# Modulo_vers_o_10.net
KiCad netlist of a schematic drawn in EAGLE
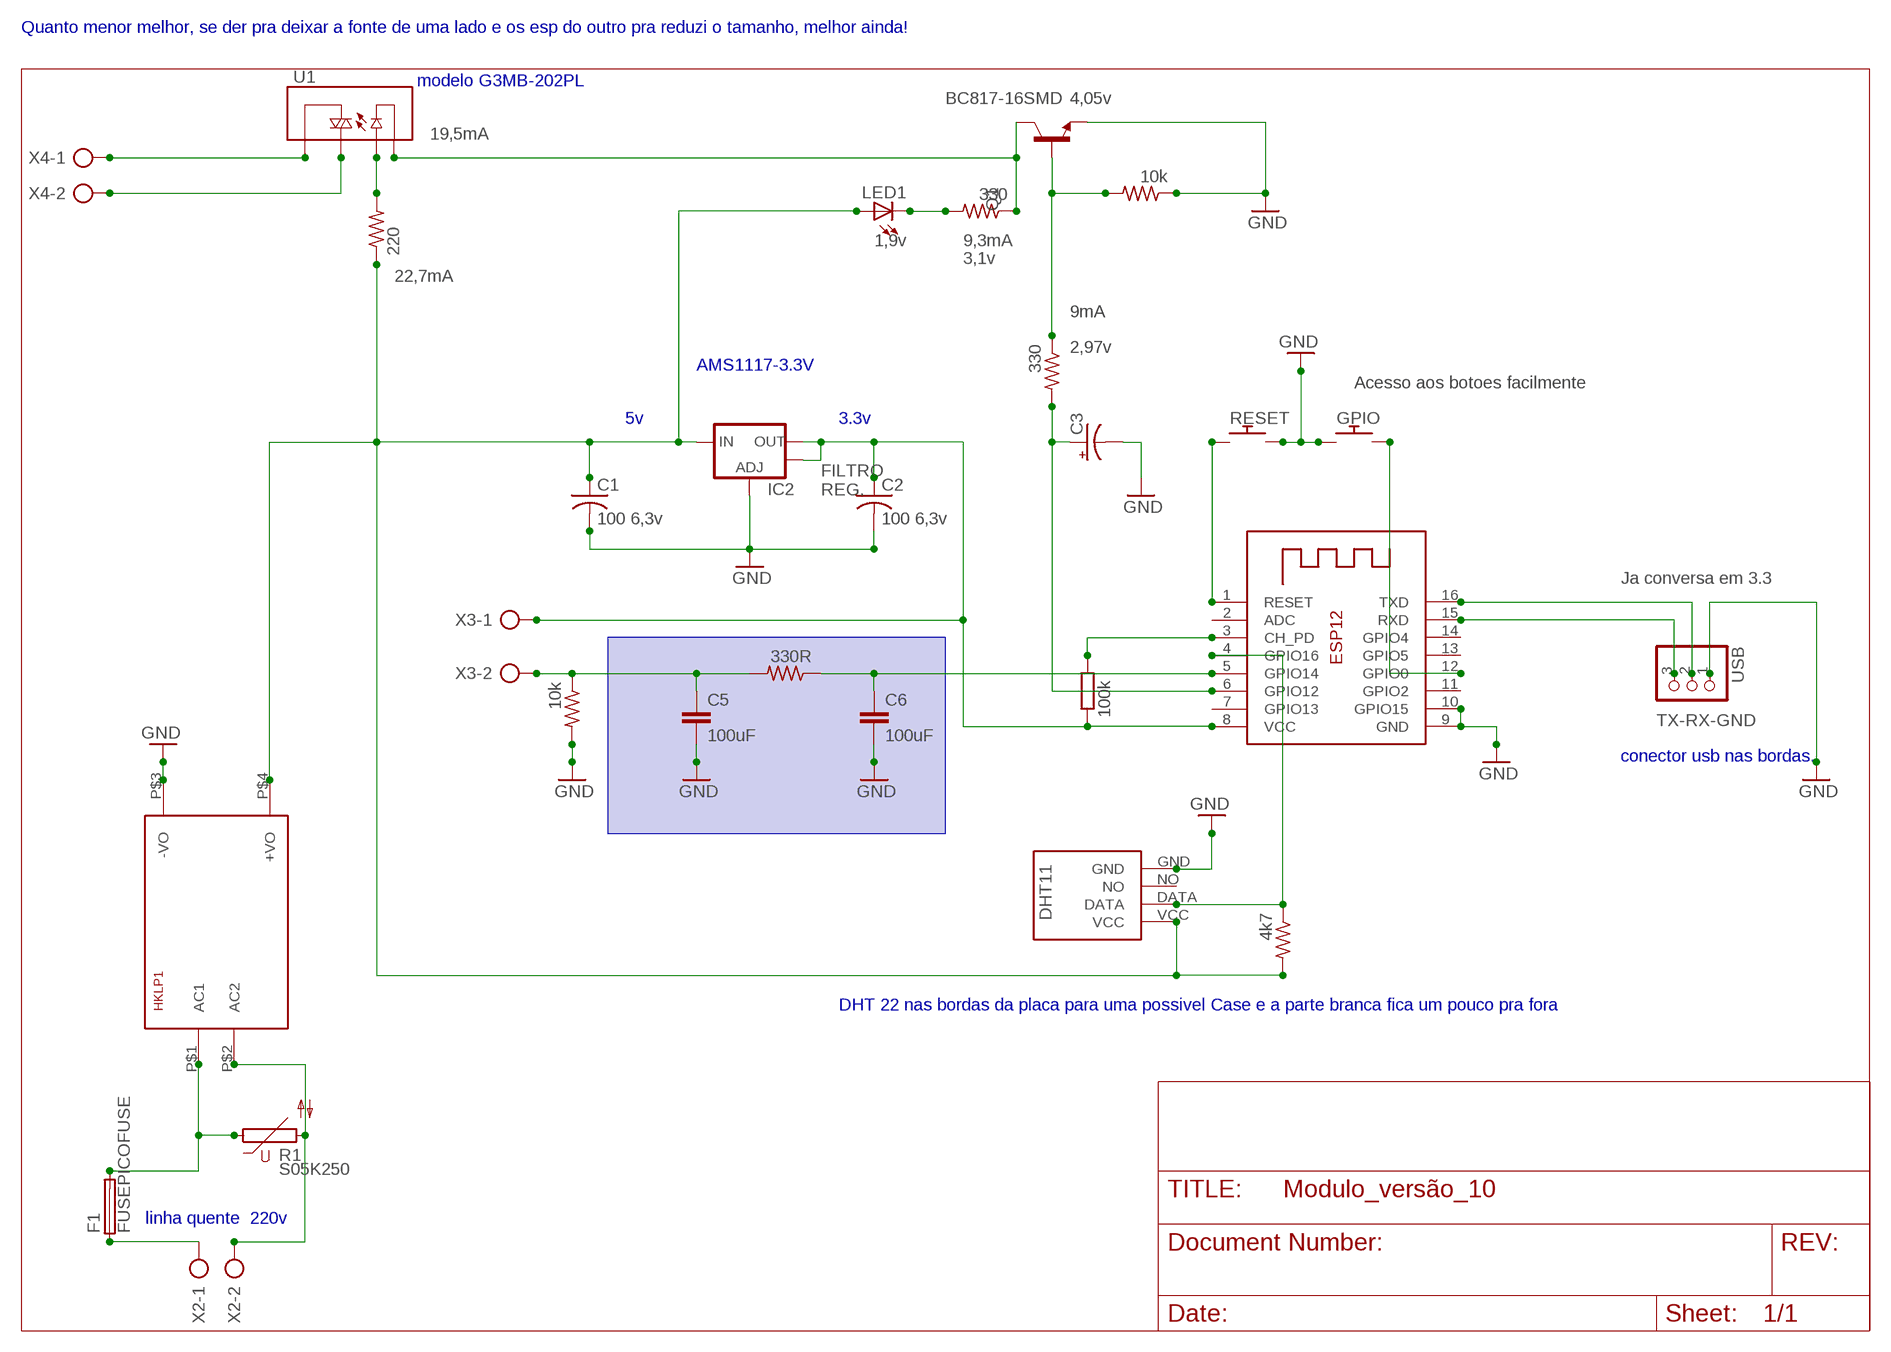
[diagram p0: schematic, sheet 1]

(export (version "E")
  (design (tool "Eeschema 10.0.6"))
  (components
    (comp (ref "1")
      (value "10k")
      (footprint "eagle-import:M0805")
      (libsource (lib "eagle-import") (part "R-US_M0805"))
    )
    (comp (ref "2")
      (value "10k")
      (footprint "eagle-import:M0805")
      (libsource (lib "eagle-import") (part "R-US_M0805"))
    )
    (comp (ref "3")
      (value "100k")
      (footprint "eagle-import:M0805")
      (libsource (lib "eagle-import") (part "R-EU_M0805"))
    )
    (comp (ref "4")
      (value "330R")
      (footprint "eagle-import:M0805")
      (libsource (lib "eagle-import") (part "R-US_M0805"))
    )
    (comp (ref "5")
      (value "330")
      (footprint "eagle-import:M0805")
      (libsource (lib "eagle-import") (part "R-US_M0805"))
    )
    (comp (ref "6")
      (value "220")
      (footprint "eagle-import:M0805")
      (libsource (lib "eagle-import") (part "R-US_M0805"))
    )
    (comp (ref "7")
      (value "330")
      (footprint "eagle-import:M0805")
      (libsource (lib "eagle-import") (part "R-US_M0805"))
    )
    (comp (ref "8")
      (value "4k7")
      (footprint "eagle-import:M0805")
      (libsource (lib "eagle-import") (part "R-US_M0805"))
    )
    (comp (ref "C1")
      (value "100 6,3v")
      (footprint "eagle-import:C0805")
      (libsource (lib "eagle-import") (part "C-USC0805"))
    )
    (comp (ref "C2")
      (value "100 6,3v")
      (footprint "eagle-import:C0805")
      (libsource (lib "eagle-import") (part "C-USC0805"))
    )
    (comp (ref "C3")
      (value "CPOL-US153CLV-0605")
      (footprint "eagle-import:153CLV-0605")
      (libsource (lib "eagle-import") (part "CPOL-US153CLV-0605"))
    )
    (comp (ref "C5")
      (value "100uF")
      (footprint "eagle-import:C0805")
      (libsource (lib "eagle-import") (part "C-EUC0805"))
    )
    (comp (ref "C6")
      (value "100uF")
      (footprint "eagle-import:C0805")
      (libsource (lib "eagle-import") (part "C-EUC0805"))
    )
    (comp (ref "F1")
      (value "FUSEPICOFUSE")
      (footprint "eagle-import:PICOFUSE")
      (libsource (lib "eagle-import") (part "FUSEPICOFUSE"))
    )
    (comp (ref "GPIO")
      (value "GPIO")
      (footprint "eagle-import:TACT_PANA-EVQ")
      (libsource (lib "eagle-import") (part "SWITCH_PUSHBUTTONEVQ-PE"))
    )
    (comp (ref "HKLP1")
      (value "HKLPM01")
      (footprint "eagle-import:HKLPM01")
      (libsource (lib "eagle-import") (part "HKLPM01"))
    )
    (comp (ref "IC2")
      (value "V_REG_LM1117SOT223")
      (footprint "eagle-import:SOT223")
      (libsource (lib "eagle-import") (part "V_REG_LM1117SOT223"))
    )
    (comp (ref "LED1")
      (value "LEDCHIPLED_0805")
      (footprint "eagle-import:CHIPLED_0805")
      (libsource (lib "eagle-import") (part "LEDCHIPLED_0805"))
    )
    (comp (ref "Q1")
      (value "BC817-16SMD")
      (footprint "eagle-import:SOT23-BEC")
      (libsource (lib "eagle-import") (part "BC817SMD-16"))
    )
    (comp (ref "R1")
      (value "S05K250")
      (footprint "eagle-import:S05K250")
      (libsource (lib "eagle-import") (part "S05K250"))
    )
    (comp (ref "RESET")
      (value "RESET")
      (footprint "eagle-import:TACT_PANA-EVQ")
      (libsource (lib "eagle-import") (part "SWITCH_PUSHBUTTONEVQ-PE"))
    )
    (comp (ref "U$1")
      (value "DHT11-PION.")
      (footprint "eagle-import:DHT11-PION.")
      (libsource (lib "eagle-import") (part "DHT11-PION."))
    )
    (comp (ref "U1")
      (value "RELAY-SOLIDSTATEPTH")
      (footprint "eagle-import:RELAY-S108T02")
      (libsource (lib "eagle-import") (part "RELAY-SOLIDSTATEPTH"))
    )
    (comp (ref "USB")
      (value "PINHD-1X3")
      (footprint "eagle-import:1X03")
      (libsource (lib "eagle-import") (part "PINHD-1X3"))
    )
    (comp (ref "X2")
      (value "AK500/2")
      (footprint "eagle-import:AK500_2")
      (libsource (lib "eagle-import") (part "AK500/2"))
    )
    (comp (ref "X3")
      (value "AK500/2")
      (footprint "eagle-import:AK500_2")
      (libsource (lib "eagle-import") (part "AK500/2"))
    )
    (comp (ref "X4")
      (value "AK500/2")
      (footprint "eagle-import:AK500_2")
      (libsource (lib "eagle-import") (part "AK500/2"))
    )
    (comp (ref "X5")
      (value "ESP-12")
      (footprint "eagle-import:ESP-12")
      (libsource (lib "eagle-import") (part "ESP-12"))
    )
  )
  (nets
    (net (code "1") (name "GND") (class "Default")
      (node (ref "1") (pin "1") (pinfunction "1_1") (pintype "passive"))
      (node (ref "2") (pin "2") (pinfunction "2_2") (pintype "passive"))
      (node (ref "C1") (pin "2") (pinfunction "2_2") (pintype "passive"))
      (node (ref "C2") (pin "2") (pinfunction "2_2") (pintype "passive"))
      (node (ref "C3") (pin "-") (pinfunction "-_-") (pintype "passive"))
      (node (ref "C5") (pin "2") (pinfunction "2_2") (pintype "passive"))
      (node (ref "C6") (pin "2") (pinfunction "2_2") (pintype "passive"))
      (node (ref "GPIO") (pin "P$1") (pinfunction "P$1_P$1") (pintype "passive"))
      (node (ref "HKLP1") (pin "P$3") (pinfunction "-VO_P$3") (pintype "bidirectional"))
      (node (ref "IC2") (pin "1") (pinfunction "ADJ_1") (pintype "input"))
      (node (ref "Q1") (pin "E") (pinfunction "E_E") (pintype "passive"))
      (node (ref "RESET") (pin "P$2") (pinfunction "P$2_P$2") (pintype "passive"))
      (node (ref "U$1") (pin "GND") (pinfunction "GND_GND") (pintype "bidirectional"))
      (node (ref "USB") (pin "1") (pinfunction "1_1") (pintype "passive"))
      (node (ref "X5") (pin "10") (pinfunction "GPIO15_10") (pintype "bidirectional"))
      (node (ref "X5") (pin "9") (pinfunction "GND_9") (pintype "power_in"))
    )
    (net (code "2") (name "Net-(1-Pad2)") (class "Default")
      (node (ref "1") (pin "2") (pinfunction "2_2") (pintype "passive"))
      (node (ref "7") (pin "1") (pinfunction "1_1") (pintype "passive"))
      (node (ref "Q1") (pin "B") (pinfunction "B_B") (pintype "passive"))
    )
    (net (code "3") (name "Net-(5-Pad2)") (class "Default")
      (node (ref "5") (pin "2") (pinfunction "2_2") (pintype "passive"))
      (node (ref "LED1") (pin "C") (pinfunction "C_C") (pintype "passive"))
    )
    (net (code "4") (name "Net-(HKLP1-+VO)") (class "Default")
      (node (ref "6") (pin "1") (pinfunction "1_1") (pintype "passive"))
      (node (ref "8") (pin "2") (pinfunction "2_2") (pintype "passive"))
      (node (ref "C1") (pin "1") (pinfunction "1_1") (pintype "passive"))
      (node (ref "HKLP1") (pin "P$4") (pinfunction "+VO_P$4") (pintype "bidirectional"))
      (node (ref "IC2") (pin "3") (pinfunction "IN_3") (pintype "input"))
      (node (ref "LED1") (pin "A") (pinfunction "A_A") (pintype "passive"))
      (node (ref "U$1") (pin "VCC") (pinfunction "VCC_VCC") (pintype "bidirectional"))
    )
    (net (code "5") (name "Net-(HKLP1-AC1)") (class "Default")
      (node (ref "F1") (pin "2") (pinfunction "2_2") (pintype "passive"))
      (node (ref "HKLP1") (pin "P$1") (pinfunction "AC1_P$1") (pintype "bidirectional"))
      (node (ref "R1") (pin "1") (pinfunction "1_1") (pintype "passive"))
    )
    (net (code "6") (name "Net-(HKLP1-AC2)") (class "Default")
      (node (ref "HKLP1") (pin "P$2") (pinfunction "AC2_P$2") (pintype "bidirectional"))
      (node (ref "R1") (pin "2") (pinfunction "2_2") (pintype "passive"))
      (node (ref "X2") (pin "2") (pinfunction "KL_2") (pintype "passive"))
    )
    (net (code "7") (name "Net-(U1-+)") (class "Default")
      (node (ref "6") (pin "2") (pinfunction "2_2") (pintype "passive"))
      (node (ref "U1") (pin "3") (pinfunction "+_3") (pintype "bidirectional"))
    )
    (net (code "8") (name "Net-(U1--)") (class "Default")
      (node (ref "5") (pin "1") (pinfunction "1_1") (pintype "passive"))
      (node (ref "Q1") (pin "C") (pinfunction "C_C") (pintype "passive"))
      (node (ref "U1") (pin "4") (pinfunction "-_4") (pintype "bidirectional"))
    )
    (net (code "9") (name "Net-(U1-T1)") (class "Default")
      (node (ref "U1") (pin "1") (pinfunction "T1_1") (pintype "bidirectional"))
      (node (ref "X4") (pin "1") (pinfunction "KL_1") (pintype "passive"))
    )
    (net (code "10") (name "Net-(U1-T2)") (class "Default")
      (node (ref "U1") (pin "2") (pinfunction "T2_2") (pintype "bidirectional"))
      (node (ref "X4") (pin "2") (pinfunction "KL_2") (pintype "passive"))
    )
    (net (code "11") (name "Net-(X2A-KL)") (class "Default")
      (node (ref "F1") (pin "1") (pinfunction "1_1") (pintype "passive"))
      (node (ref "X2") (pin "1") (pinfunction "KL_1") (pintype "passive"))
    )
    (net (code "12") (name "Net-(X3A-KL)") (class "Default")
      (node (ref "3") (pin "1") (pinfunction "1_1") (pintype "passive"))
      (node (ref "C2") (pin "1") (pinfunction "1_1") (pintype "passive"))
      (node (ref "IC2") (pin "2") (pinfunction "OUT_2") (pintype "output"))
      (node (ref "IC2") (pin "4") (pinfunction "OUT_4") (pintype "output"))
      (node (ref "X3") (pin "1") (pinfunction "KL_1") (pintype "passive"))
      (node (ref "X5") (pin "8") (pinfunction "VCC_8") (pintype "power_in"))
    )
    (net (code "13") (name "Net-(X3B-KL)") (class "Default")
      (node (ref "2") (pin "1") (pinfunction "1_1") (pintype "passive"))
      (node (ref "4") (pin "2") (pinfunction "2_2") (pintype "passive"))
      (node (ref "C5") (pin "1") (pinfunction "1_1") (pintype "passive"))
      (node (ref "X3") (pin "2") (pinfunction "KL_2") (pintype "passive"))
    )
    (net (code "14") (name "Net-(X5-CH_PD)") (class "Default")
      (node (ref "3") (pin "2") (pinfunction "2_2") (pintype "passive"))
      (node (ref "X5") (pin "3") (pinfunction "CH_PD_3") (pintype "input"))
    )
    (net (code "15") (name "Net-(X5-GPIO0)") (class "Default")
      (node (ref "GPIO") (pin "P$2") (pinfunction "P$2_P$2") (pintype "passive"))
      (node (ref "X5") (pin "12") (pinfunction "GPIO0_12") (pintype "bidirectional"))
    )
    (net (code "16") (name "Net-(X5-GPIO12)") (class "Default")
      (node (ref "7") (pin "2") (pinfunction "2_2") (pintype "passive"))
      (node (ref "C3") (pin "+") (pinfunction "+_+") (pintype "passive"))
      (node (ref "X5") (pin "6") (pinfunction "GPIO12_6") (pintype "bidirectional"))
    )
    (net (code "17") (name "Net-(X5-GPIO14)") (class "Default")
      (node (ref "4") (pin "1") (pinfunction "1_1") (pintype "passive"))
      (node (ref "C6") (pin "1") (pinfunction "1_1") (pintype "passive"))
      (node (ref "X5") (pin "5") (pinfunction "GPIO14_5") (pintype "bidirectional"))
    )
    (net (code "18") (name "Net-(X5-GPIO16)") (class "Default")
      (node (ref "8") (pin "1") (pinfunction "1_1") (pintype "passive"))
      (node (ref "U$1") (pin "DATA") (pinfunction "DATA_DATA") (pintype "bidirectional"))
      (node (ref "X5") (pin "4") (pinfunction "GPIO16_4") (pintype "bidirectional"))
    )
    (net (code "19") (name "Net-(X5-RESET)") (class "Default")
      (node (ref "RESET") (pin "P$1") (pinfunction "P$1_P$1") (pintype "passive"))
      (node (ref "X5") (pin "1") (pinfunction "RESET_1") (pintype "input"))
    )
    (net (code "20") (name "Net-(X5-RXD)") (class "Default")
      (node (ref "USB") (pin "3") (pinfunction "3_3") (pintype "passive"))
      (node (ref "X5") (pin "15") (pinfunction "RXD_15") (pintype "input"))
    )
    (net (code "21") (name "Net-(X5-TXD)") (class "Default")
      (node (ref "USB") (pin "2") (pinfunction "2_2") (pintype "passive"))
      (node (ref "X5") (pin "16") (pinfunction "TXD_16") (pintype "output"))
    )
    (net (code "22") (name "unconnected-(U$1-PadNO)") (class "Default")
      (node (ref "U$1") (pin "NO") (pinfunction "NO_NO") (pintype "bidirectional"))
    )
    (net (code "23") (name "unconnected-(X5-ADC-Pad2)") (class "Default")
      (node (ref "X5") (pin "2") (pinfunction "ADC_2") (pintype "passive"))
    )
    (net (code "24") (name "unconnected-(X5-GPIO2-Pad11)") (class "Default")
      (node (ref "X5") (pin "11") (pinfunction "GPIO2_11") (pintype "bidirectional"))
    )
    (net (code "25") (name "unconnected-(X5-GPIO4-Pad14)") (class "Default")
      (node (ref "X5") (pin "14") (pinfunction "GPIO4_14") (pintype "bidirectional"))
    )
    (net (code "26") (name "unconnected-(X5-GPIO5-Pad13)") (class "Default")
      (node (ref "X5") (pin "13") (pinfunction "GPIO5_13") (pintype "bidirectional"))
    )
    (net (code "27") (name "unconnected-(X5-GPIO13-Pad7)") (class "Default")
      (node (ref "X5") (pin "7") (pinfunction "GPIO13_7") (pintype "bidirectional"))
    )
  )
)
